# UARTOptoCoupler.net
KiCad netlist of a schematic drawn in EAGLE
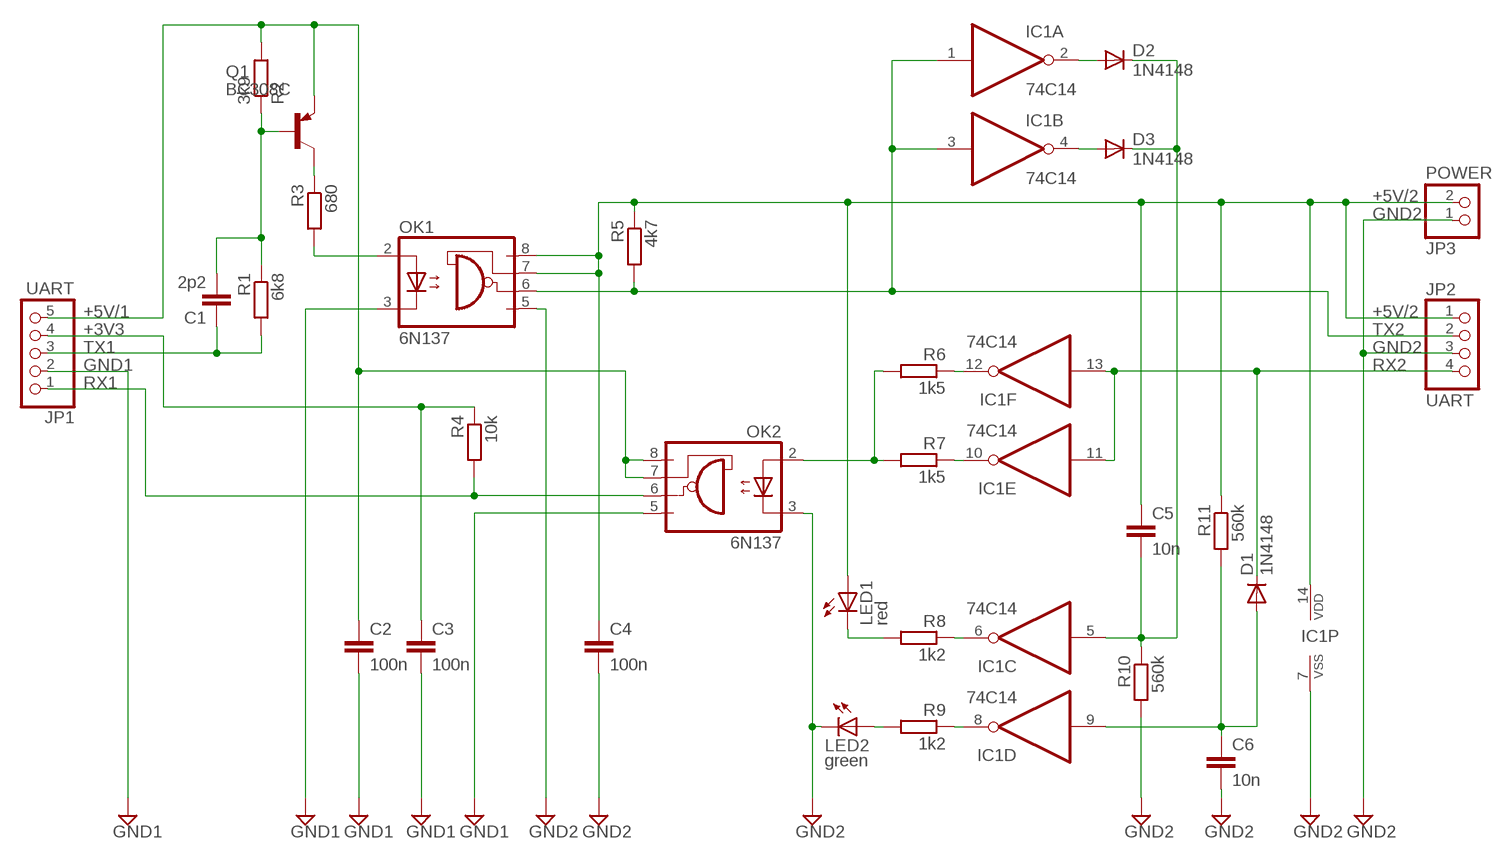
[diagram p0: schematic, sheet 1]

(export (version "E")
  (design (tool "Eeschema 10.0.6"))
  (components
    (comp (ref "C1")
      (value "2p2")
      (footprint "eagle-import:C025-024X044")
      (libsource (lib "eagle-import") (part "C-EU025-024X044"))
    )
    (comp (ref "C2")
      (value "100n")
      (footprint "eagle-import:C050-025X075")
      (libsource (lib "eagle-import") (part "C-EU050-025X075"))
    )
    (comp (ref "C3")
      (value "100n")
      (footprint "eagle-import:C050-025X075")
      (libsource (lib "eagle-import") (part "C-EU050-025X075"))
    )
    (comp (ref "C4")
      (value "100n")
      (footprint "eagle-import:C050-025X075")
      (libsource (lib "eagle-import") (part "C-EU050-025X075"))
    )
    (comp (ref "C5")
      (value "10n")
      (footprint "eagle-import:C050-025X075")
      (libsource (lib "eagle-import") (part "C-EU050-025X075"))
    )
    (comp (ref "C6")
      (value "10n")
      (footprint "eagle-import:C050-025X075")
      (libsource (lib "eagle-import") (part "C-EU050-025X075"))
    )
    (comp (ref "D1")
      (value "1N4148")
      (footprint "eagle-import:DO35-10")
      (libsource (lib "eagle-import") (part "1N4148DO35-10"))
    )
    (comp (ref "D2")
      (value "1N4148")
      (footprint "eagle-import:DO35-10")
      (libsource (lib "eagle-import") (part "1N4148DO35-10"))
    )
    (comp (ref "D3")
      (value "1N4148")
      (footprint "eagle-import:DO35-10")
      (libsource (lib "eagle-import") (part "1N4148DO35-10"))
    )
    (comp (ref "IC1")
      (value "74C14")
      (footprint "eagle-import:DIL14")
      (libsource (lib "eagle-import") (part "4584N"))
    )
    (comp (ref "JP1")
      (value "UART")
      (footprint "eagle-import:1X05")
      (libsource (lib "eagle-import") (part "PINHD-1X5"))
    )
    (comp (ref "JP2")
      (value "UART")
      (footprint "eagle-import:1X04_90")
      (libsource (lib "eagle-import") (part "PINHD-1X4/90"))
    )
    (comp (ref "JP3")
      (value "POWER")
      (footprint "eagle-import:1X02")
      (libsource (lib "eagle-import") (part "PINHD-1X2"))
    )
    (comp (ref "LED1")
      (value "red")
      (footprint "eagle-import:LED3MM")
      (libsource (lib "eagle-import") (part "LED3MM"))
    )
    (comp (ref "LED2")
      (value "green")
      (footprint "eagle-import:LED3MM")
      (libsource (lib "eagle-import") (part "LED3MM"))
    )
    (comp (ref "OK1")
      (value "6N137")
      (footprint "eagle-import:DIL08")
      (libsource (lib "eagle-import") (part "6N137"))
    )
    (comp (ref "OK2")
      (value "6N137")
      (footprint "eagle-import:DIL08")
      (libsource (lib "eagle-import") (part "6N137"))
    )
    (comp (ref "Q1")
      (value "BC308C")
      (footprint "eagle-import:TO92")
      (libsource (lib "eagle-import") (part "BC307"))
    )
    (comp (ref "R1")
      (value "6k8")
      (footprint "eagle-import:0207_10")
      (libsource (lib "eagle-import") (part "R-EU_0207/10"))
    )
    (comp (ref "R2")
      (value "3k9")
      (footprint "eagle-import:0207_10")
      (libsource (lib "eagle-import") (part "R-EU_0207/10"))
    )
    (comp (ref "R3")
      (value "680")
      (footprint "eagle-import:0207_10")
      (libsource (lib "eagle-import") (part "R-EU_0207/10"))
    )
    (comp (ref "R4")
      (value "10k")
      (footprint "eagle-import:0207_10")
      (libsource (lib "eagle-import") (part "R-EU_0207/10"))
    )
    (comp (ref "R5")
      (value "4k7")
      (footprint "eagle-import:0207_10")
      (libsource (lib "eagle-import") (part "R-EU_0207/10"))
    )
    (comp (ref "R6")
      (value "1k5")
      (footprint "eagle-import:0207_10")
      (libsource (lib "eagle-import") (part "R-EU_0207/10"))
    )
    (comp (ref "R7")
      (value "1k5")
      (footprint "eagle-import:0207_10")
      (libsource (lib "eagle-import") (part "R-EU_0207/10"))
    )
    (comp (ref "R8")
      (value "1k2")
      (footprint "eagle-import:0207_10")
      (libsource (lib "eagle-import") (part "R-EU_0207/10"))
    )
    (comp (ref "R9")
      (value "1k2")
      (footprint "eagle-import:0207_10")
      (libsource (lib "eagle-import") (part "R-EU_0207/10"))
    )
    (comp (ref "R10")
      (value "560k")
      (footprint "eagle-import:0207_10")
      (libsource (lib "eagle-import") (part "R-EU_0207/10"))
    )
    (comp (ref "R11")
      (value "560k")
      (footprint "eagle-import:0207_10")
      (libsource (lib "eagle-import") (part "R-EU_0207/10"))
    )
  )
  (nets
    (net (code "1") (name "/+3V3") (class "Default")
      (node (ref "C3") (pin "1") (pinfunction "1_1") (pintype "passive"))
      (node (ref "JP1") (pin "4") (pinfunction "4_4") (pintype "passive"))
      (node (ref "R4") (pin "1") (pinfunction "1_1") (pintype "passive"))
    )
    (net (code "2") (name "/+5V{slash}1") (class "Default")
      (node (ref "C2") (pin "1") (pinfunction "1_1") (pintype "passive"))
      (node (ref "JP1") (pin "5") (pinfunction "5_5") (pintype "passive"))
      (node (ref "OK2") (pin "7") (pinfunction "VE_7") (pintype "passive"))
      (node (ref "OK2") (pin "8") (pinfunction "VCC_8") (pintype "passive"))
      (node (ref "Q1") (pin "1") (pinfunction "E_1") (pintype "passive"))
      (node (ref "R2") (pin "2") (pinfunction "2_2") (pintype "passive"))
    )
    (net (code "3") (name "/+5V{slash}2") (class "Default")
      (node (ref "C4") (pin "1") (pinfunction "1_1") (pintype "passive"))
      (node (ref "C5") (pin "1") (pinfunction "1_1") (pintype "passive"))
      (node (ref "IC1") (pin "14") (pinfunction "VDD_14") (pintype "power_in"))
      (node (ref "JP2") (pin "1") (pinfunction "1_1") (pintype "passive"))
      (node (ref "JP3") (pin "2") (pinfunction "2_2") (pintype "passive"))
      (node (ref "LED1") (pin "A") (pinfunction "A_A") (pintype "passive"))
      (node (ref "OK1") (pin "7") (pinfunction "VE_7") (pintype "passive"))
      (node (ref "OK1") (pin "8") (pinfunction "VCC_8") (pintype "passive"))
      (node (ref "R11") (pin "1") (pinfunction "1_1") (pintype "passive"))
      (node (ref "R5") (pin "1") (pinfunction "1_1") (pintype "passive"))
    )
    (net (code "4") (name "/RX1") (class "Default")
      (node (ref "JP1") (pin "1") (pinfunction "1_1") (pintype "passive"))
      (node (ref "OK2") (pin "6") (pinfunction "VO_6") (pintype "passive"))
      (node (ref "R4") (pin "2") (pinfunction "2_2") (pintype "passive"))
    )
    (net (code "5") (name "/RX2") (class "Default")
      (node (ref "D1") (pin "C") (pinfunction "C_C") (pintype "passive"))
      (node (ref "IC1") (pin "11") (pinfunction "I_11") (pintype "input"))
      (node (ref "IC1") (pin "13") (pinfunction "I_13") (pintype "input"))
      (node (ref "JP2") (pin "4") (pinfunction "4_4") (pintype "passive"))
    )
    (net (code "6") (name "/TX1") (class "Default")
      (node (ref "C1") (pin "1") (pinfunction "1_1") (pintype "passive"))
      (node (ref "JP1") (pin "3") (pinfunction "3_3") (pintype "passive"))
      (node (ref "R1") (pin "2") (pinfunction "2_2") (pintype "passive"))
    )
    (net (code "7") (name "/TX2") (class "Default")
      (node (ref "IC1") (pin "1") (pinfunction "I_1") (pintype "input"))
      (node (ref "IC1") (pin "3") (pinfunction "I_3") (pintype "input"))
      (node (ref "JP2") (pin "2") (pinfunction "2_2") (pintype "passive"))
      (node (ref "OK1") (pin "6") (pinfunction "VO_6") (pintype "passive"))
      (node (ref "R5") (pin "2") (pinfunction "2_2") (pintype "passive"))
    )
    (net (code "8") (name "GND1") (class "Default")
      (node (ref "C2") (pin "2") (pinfunction "2_2") (pintype "passive"))
      (node (ref "C3") (pin "2") (pinfunction "2_2") (pintype "passive"))
      (node (ref "JP1") (pin "2") (pinfunction "2_2") (pintype "passive"))
      (node (ref "OK1") (pin "3") (pinfunction "C_3") (pintype "passive"))
      (node (ref "OK2") (pin "5") (pinfunction "GND_5") (pintype "passive"))
    )
    (net (code "9") (name "GND2") (class "Default")
      (node (ref "C4") (pin "2") (pinfunction "2_2") (pintype "passive"))
      (node (ref "C6") (pin "2") (pinfunction "2_2") (pintype "passive"))
      (node (ref "IC1") (pin "7") (pinfunction "VSS_7") (pintype "power_in"))
      (node (ref "JP2") (pin "3") (pinfunction "3_3") (pintype "passive"))
      (node (ref "JP3") (pin "1") (pinfunction "1_1") (pintype "passive"))
      (node (ref "LED2") (pin "K") (pinfunction "C_K") (pintype "passive"))
      (node (ref "OK1") (pin "5") (pinfunction "GND_5") (pintype "passive"))
      (node (ref "OK2") (pin "3") (pinfunction "C_3") (pintype "passive"))
      (node (ref "R10") (pin "2") (pinfunction "2_2") (pintype "passive"))
    )
    (net (code "10") (name "Net-(IC1A-O)") (class "Default")
      (node (ref "D2") (pin "A") (pinfunction "A_A") (pintype "passive"))
      (node (ref "IC1") (pin "2") (pinfunction "O_2") (pintype "output"))
    )
    (net (code "11") (name "Net-(IC1B-O)") (class "Default")
      (node (ref "D3") (pin "A") (pinfunction "A_A") (pintype "passive"))
      (node (ref "IC1") (pin "4") (pinfunction "O_4") (pintype "output"))
    )
    (net (code "12") (name "Net-(IC1C-I)") (class "Default")
      (node (ref "C5") (pin "2") (pinfunction "2_2") (pintype "passive"))
      (node (ref "D2") (pin "C") (pinfunction "C_C") (pintype "passive"))
      (node (ref "D3") (pin "C") (pinfunction "C_C") (pintype "passive"))
      (node (ref "IC1") (pin "5") (pinfunction "I_5") (pintype "input"))
      (node (ref "R10") (pin "1") (pinfunction "1_1") (pintype "passive"))
    )
    (net (code "13") (name "Net-(IC1C-O)") (class "Default")
      (node (ref "IC1") (pin "6") (pinfunction "O_6") (pintype "output"))
      (node (ref "R8") (pin "1") (pinfunction "1_1") (pintype "passive"))
    )
    (net (code "14") (name "Net-(IC1D-I)") (class "Default")
      (node (ref "C6") (pin "1") (pinfunction "1_1") (pintype "passive"))
      (node (ref "D1") (pin "A") (pinfunction "A_A") (pintype "passive"))
      (node (ref "IC1") (pin "9") (pinfunction "I_9") (pintype "input"))
      (node (ref "R11") (pin "2") (pinfunction "2_2") (pintype "passive"))
    )
    (net (code "15") (name "Net-(IC1D-O)") (class "Default")
      (node (ref "IC1") (pin "8") (pinfunction "O_8") (pintype "output"))
      (node (ref "R9") (pin "1") (pinfunction "1_1") (pintype "passive"))
    )
    (net (code "16") (name "Net-(IC1E-O)") (class "Default")
      (node (ref "IC1") (pin "10") (pinfunction "O_10") (pintype "output"))
      (node (ref "R7") (pin "1") (pinfunction "1_1") (pintype "passive"))
    )
    (net (code "17") (name "Net-(IC1F-O)") (class "Default")
      (node (ref "IC1") (pin "12") (pinfunction "O_12") (pintype "output"))
      (node (ref "R6") (pin "1") (pinfunction "1_1") (pintype "passive"))
    )
    (net (code "18") (name "Net-(LED1-C)") (class "Default")
      (node (ref "LED1") (pin "K") (pinfunction "C_K") (pintype "passive"))
      (node (ref "R8") (pin "2") (pinfunction "2_2") (pintype "passive"))
    )
    (net (code "19") (name "Net-(LED2-PadA)") (class "Default")
      (node (ref "LED2") (pin "A") (pinfunction "A_A") (pintype "passive"))
      (node (ref "R9") (pin "2") (pinfunction "2_2") (pintype "passive"))
    )
    (net (code "20") (name "Net-(OK1-A)") (class "Default")
      (node (ref "OK1") (pin "2") (pinfunction "A_2") (pintype "passive"))
      (node (ref "R3") (pin "2") (pinfunction "2_2") (pintype "passive"))
    )
    (net (code "21") (name "Net-(OK2-A)") (class "Default")
      (node (ref "OK2") (pin "2") (pinfunction "A_2") (pintype "passive"))
      (node (ref "R6") (pin "2") (pinfunction "2_2") (pintype "passive"))
      (node (ref "R7") (pin "2") (pinfunction "2_2") (pintype "passive"))
    )
    (net (code "22") (name "Net-(Q1-B)") (class "Default")
      (node (ref "C1") (pin "2") (pinfunction "2_2") (pintype "passive"))
      (node (ref "Q1") (pin "2") (pinfunction "B_2") (pintype "passive"))
      (node (ref "R1") (pin "1") (pinfunction "1_1") (pintype "passive"))
      (node (ref "R2") (pin "1") (pinfunction "1_1") (pintype "passive"))
    )
    (net (code "23") (name "Net-(Q1-C)") (class "Default")
      (node (ref "Q1") (pin "3") (pinfunction "C_3") (pintype "passive"))
      (node (ref "R3") (pin "1") (pinfunction "1_1") (pintype "passive"))
    )
  )
)
